# ADC.net
KiCad netlist of a schematic drawn in Altium Designer
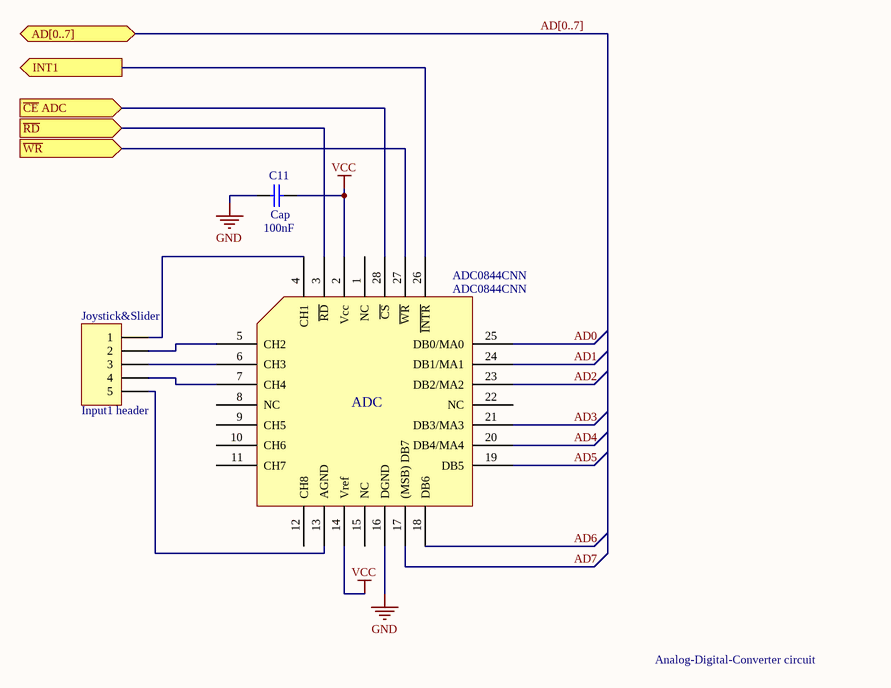
[diagram p0: ADC.SchDoc]

(export (version "E")
  (design (tool "Eeschema 10.0.6"))
  (components
    (comp (ref "ADC0844CNN")
      (value "ADC0844CNN")
      (footprint "ADC0844CNN PLCC 28-PIN")
      (description "ADC - Analogue to Digital Converter")
      (libsource (lib "IIDKLib") (part "ADC0844CNN"))
    )
    (comp (ref "C11")
      (value "Cap")
      (footprint "C1210")
      (description "Capacitor (Semiconductor SIM Model)")
      (fields (field (name "ALTIUM_VALUE") "100nF") (field (name "PUBLISHER") "Altium Limited"))
      (libsource (lib "Miscellaneous Devices") (part "Cap Semi"))
    )
    (comp (ref "Joystick&Slider")
      (value "Input1 header")
      (footprint "HDR1X5")
      (description "Header, 5-Pin")
      (fields (field (name "PUBLISHER") "Altium Limited"))
      (libsource (lib "Miscellaneous Connectors") (part "Header 5"))
    )
  )
  (nets
    (net (code "1") (name "/AD0") (class "Default")
      (node (ref "ADC0844CNN") (pin "25") (pinfunction "DB0/MA0_25") (pintype "passive"))
    )
    (net (code "2") (name "/AD1") (class "Default")
      (node (ref "ADC0844CNN") (pin "24") (pinfunction "DB1/MA1_24") (pintype "passive"))
    )
    (net (code "3") (name "/AD2") (class "Default")
      (node (ref "ADC0844CNN") (pin "23") (pinfunction "DB2/MA2_23") (pintype "passive"))
    )
    (net (code "4") (name "/AD3") (class "Default")
      (node (ref "ADC0844CNN") (pin "21") (pinfunction "DB3/MA3_21") (pintype "passive"))
    )
    (net (code "5") (name "/AD4") (class "Default")
      (node (ref "ADC0844CNN") (pin "20") (pinfunction "DB4/MA4_20") (pintype "passive"))
    )
    (net (code "6") (name "/AD5") (class "Default")
      (node (ref "ADC0844CNN") (pin "19") (pinfunction "DB5_19") (pintype "passive"))
    )
    (net (code "7") (name "/AD6") (class "Default")
      (node (ref "ADC0844CNN") (pin "18") (pinfunction "DB6_18") (pintype "passive"))
    )
    (net (code "8") (name "/AD7") (class "Default")
      (node (ref "ADC0844CNN") (pin "17") (pinfunction "(MSB)_DB7_17") (pintype "passive"))
    )
    (net (code "10") (name "/INT1") (class "Default")
      (node (ref "ADC0844CNN") (pin "26") (pinfunction "~{INTR}_26") (pintype "passive"))
    )
    (net (code "11") (name "/~{CE} ADC") (class "Default")
      (node (ref "ADC0844CNN") (pin "28") (pinfunction "~{CS}_28") (pintype "passive"))
    )
    (net (code "12") (name "/~{RD}") (class "Default")
      (node (ref "ADC0844CNN") (pin "3") (pinfunction "~{RD}_3") (pintype "passive"))
    )
    (net (code "13") (name "/~{WR}") (class "Default")
      (node (ref "ADC0844CNN") (pin "27") (pinfunction "~{WR}_27") (pintype "passive"))
    )
    (net (code "14") (name "GND") (class "Default")
      (node (ref "ADC0844CNN") (pin "16") (pinfunction "DGND_16") (pintype "power_in"))
      (node (ref "C11") (pin "2") (pinfunction "2_2") (pintype "passive"))
    )
    (net (code "15") (name "Net-(ADC0844CNN-AGND)") (class "Default")
      (node (ref "ADC0844CNN") (pin "13") (pinfunction "AGND_13") (pintype "power_in"))
      (node (ref "Joystick&Slider") (pin "5") (pinfunction "5_5") (pintype "passive"))
    )
    (net (code "16") (name "Net-(ADC0844CNN-CH1)") (class "Default")
      (node (ref "ADC0844CNN") (pin "4") (pinfunction "CH1_4") (pintype "passive"))
      (node (ref "Joystick&Slider") (pin "1") (pinfunction "1_1") (pintype "passive"))
    )
    (net (code "17") (name "Net-(ADC0844CNN-CH2)") (class "Default")
      (node (ref "ADC0844CNN") (pin "5") (pinfunction "CH2_5") (pintype "passive"))
      (node (ref "Joystick&Slider") (pin "2") (pinfunction "2_2") (pintype "passive"))
    )
    (net (code "18") (name "Net-(ADC0844CNN-CH3)") (class "Default")
      (node (ref "ADC0844CNN") (pin "6") (pinfunction "CH3_6") (pintype "passive"))
      (node (ref "Joystick&Slider") (pin "3") (pinfunction "3_3") (pintype "passive"))
    )
    (net (code "19") (name "Net-(ADC0844CNN-CH4)") (class "Default")
      (node (ref "ADC0844CNN") (pin "7") (pinfunction "CH4_7") (pintype "passive"))
      (node (ref "Joystick&Slider") (pin "4") (pinfunction "4_4") (pintype "passive"))
    )
    (net (code "20") (name "VCC") (class "Default")
      (node (ref "ADC0844CNN") (pin "14") (pinfunction "Vref_14") (pintype "passive"))
      (node (ref "ADC0844CNN") (pin "2") (pinfunction "Vcc_2") (pintype "passive"))
      (node (ref "C11") (pin "1") (pinfunction "1_1") (pintype "passive"))
    )
    (net (code "21") (name "unconnected-(ADC0844CNN-CH5-Pad9)") (class "Default")
      (node (ref "ADC0844CNN") (pin "9") (pinfunction "CH5_9") (pintype "passive"))
    )
    (net (code "22") (name "unconnected-(ADC0844CNN-CH6-Pad10)") (class "Default")
      (node (ref "ADC0844CNN") (pin "10") (pinfunction "CH6_10") (pintype "passive"))
    )
    (net (code "23") (name "unconnected-(ADC0844CNN-CH7-Pad11)") (class "Default")
      (node (ref "ADC0844CNN") (pin "11") (pinfunction "CH7_11") (pintype "passive"))
    )
    (net (code "24") (name "unconnected-(ADC0844CNN-CH8-Pad12)") (class "Default")
      (node (ref "ADC0844CNN") (pin "12") (pinfunction "CH8_12") (pintype "passive"))
    )
    (net (code "25") (name "unconnected-(ADC0844CNN-NC-Pad1)") (class "Default")
      (node (ref "ADC0844CNN") (pin "1") (pinfunction "NC_1") (pintype "passive"))
    )
    (net (code "26") (name "unconnected-(ADC0844CNN-NC-Pad8)") (class "Default")
      (node (ref "ADC0844CNN") (pin "8") (pinfunction "NC_8") (pintype "passive"))
    )
    (net (code "27") (name "unconnected-(ADC0844CNN-NC-Pad15)") (class "Default")
      (node (ref "ADC0844CNN") (pin "15") (pinfunction "NC_15") (pintype "passive"))
    )
    (net (code "28") (name "unconnected-(ADC0844CNN-NC-Pad22)") (class "Default")
      (node (ref "ADC0844CNN") (pin "22") (pinfunction "NC_22") (pintype "passive"))
    )
  )
)
